# SCH_NFC-Card-Super-Shiva_2024-10-10.net
KiCad netlist of a schematic drawn in EasyEDA
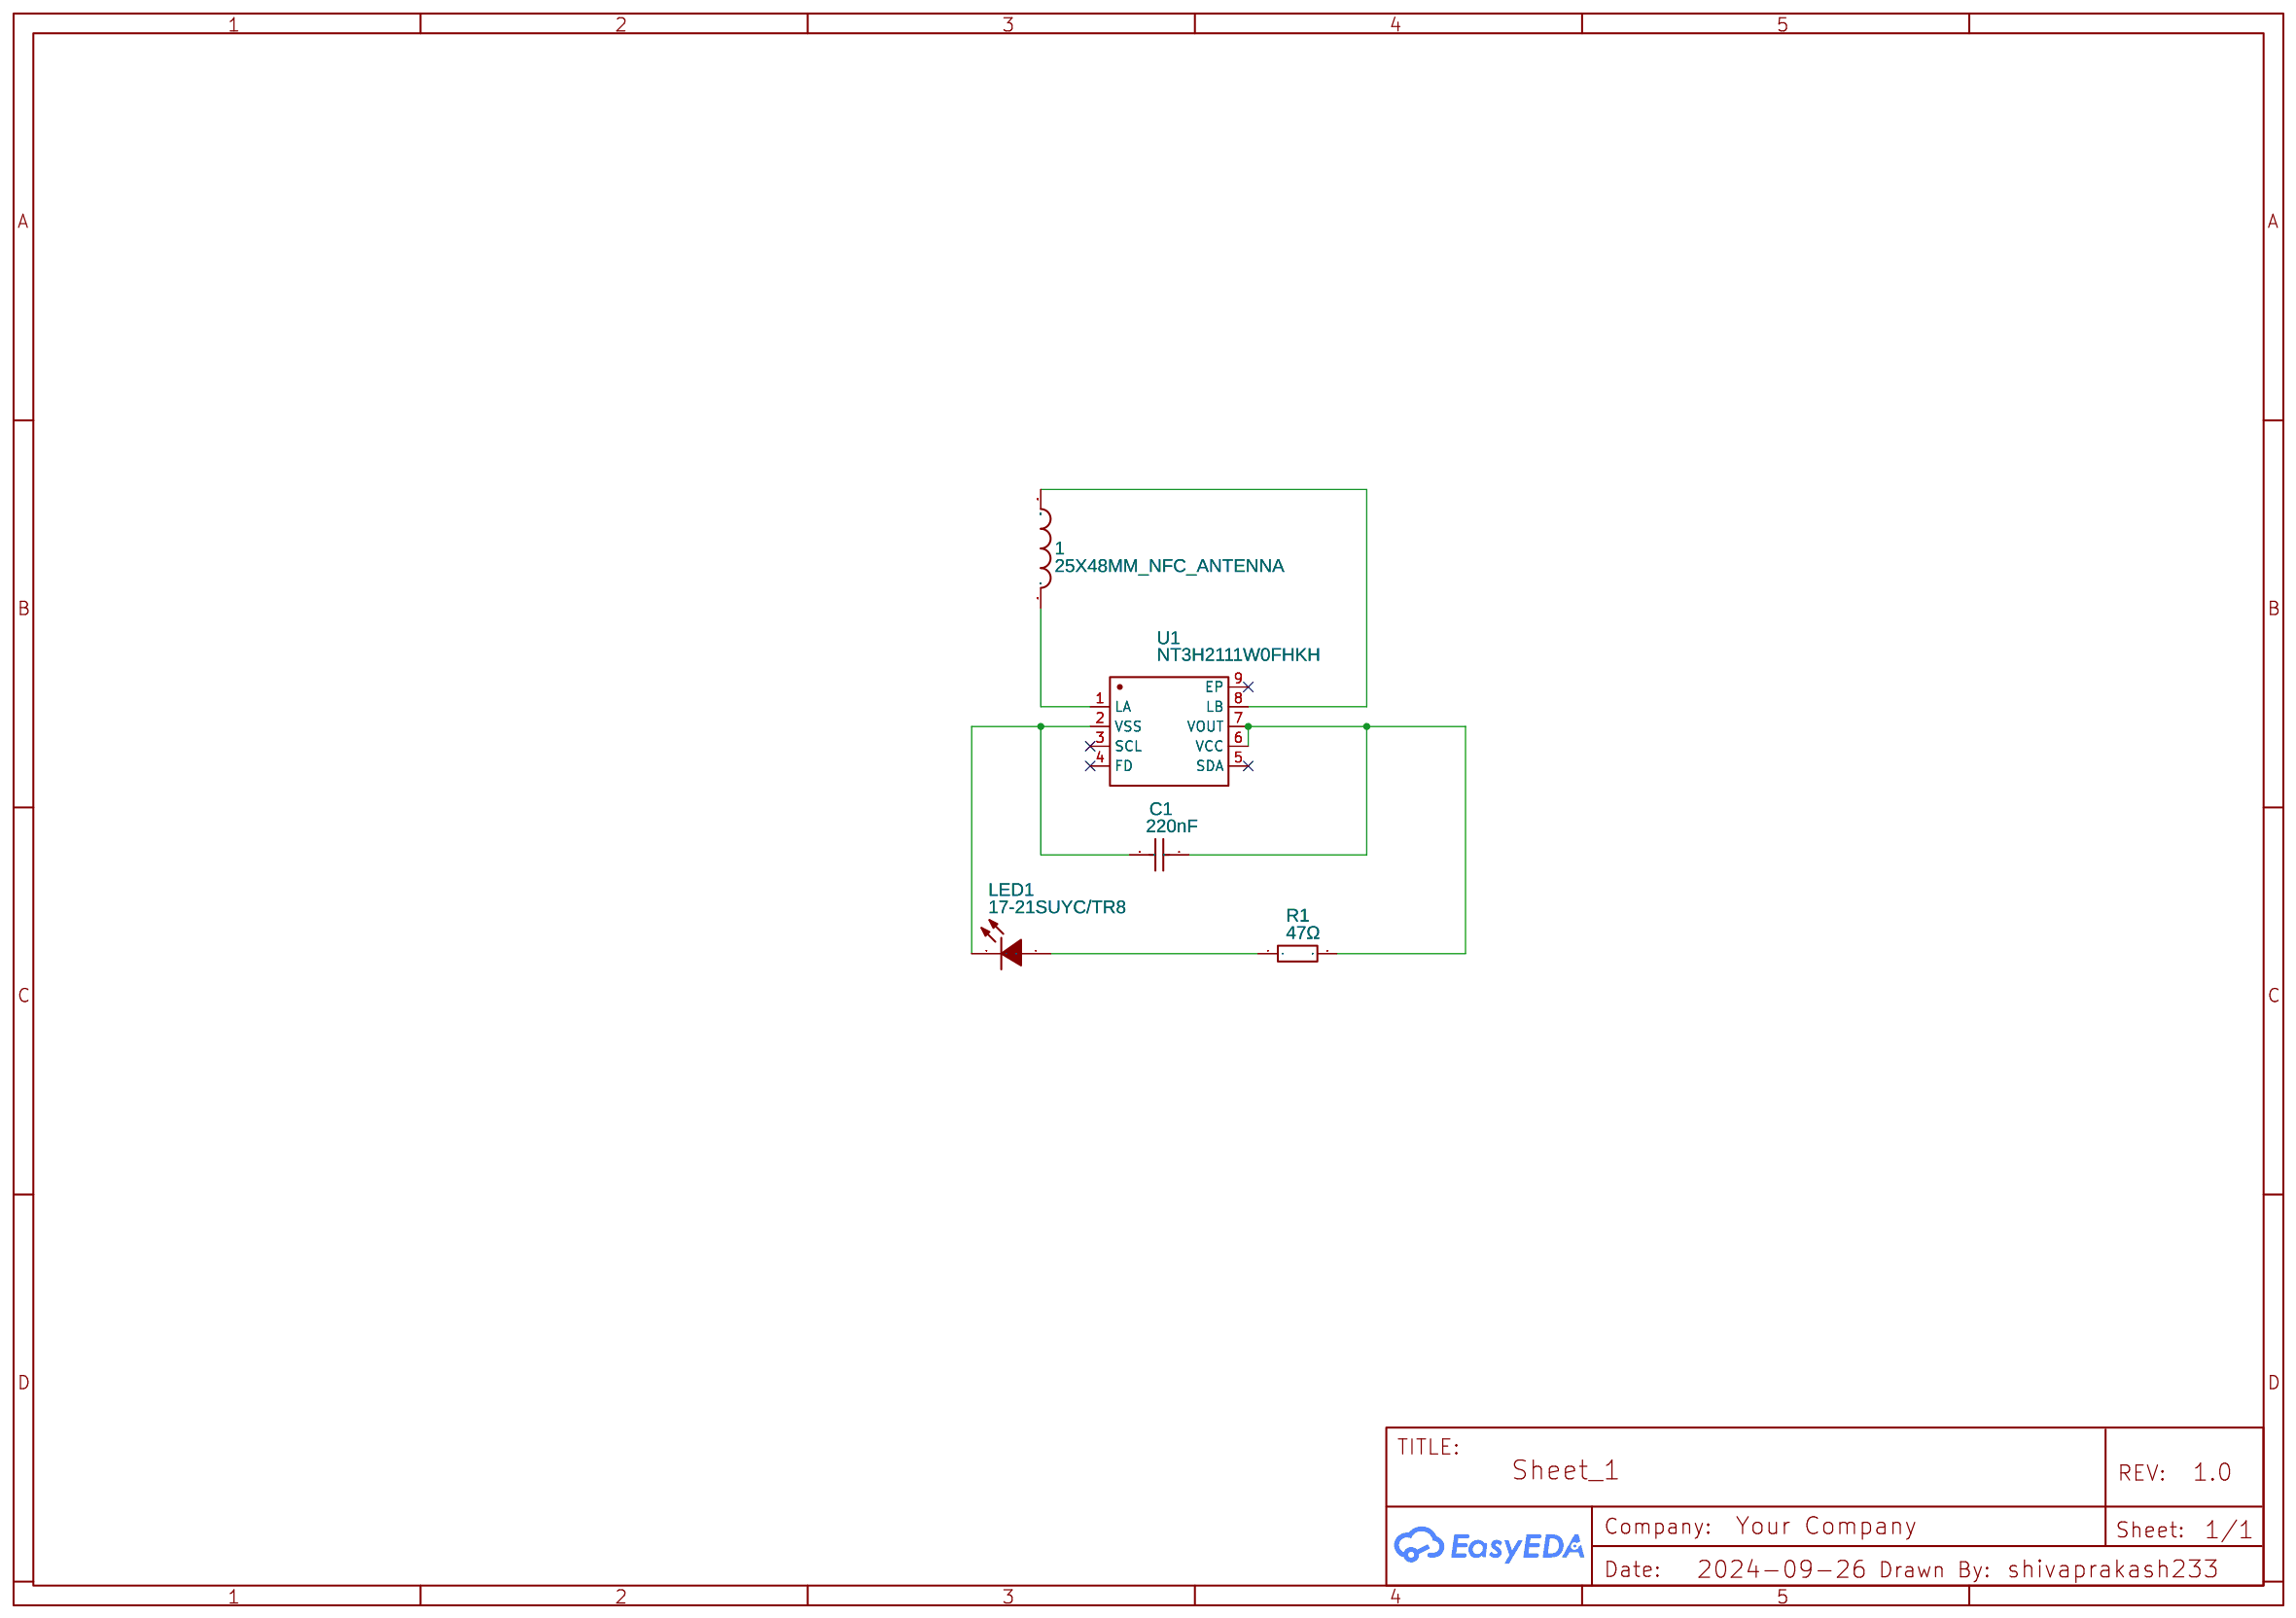
[diagram p0: schematic sheet]

(export (version "E")
  (design (tool "Eeschema 10.0.6"))
  (components
    (comp (ref "1") (value "25X48MM_NFC_ANTENNA") (libsource (lib "") (part "25X48MM_NFC_ANTENNA")))
    (comp (ref "C1")
      (value "220nF")
      (fields
        (field (name "Manufacturer Part") "CL10B224KA8NNNC")
        (field (name "Manufacturer") "SAMSUNG(三星)")
      )
      (libsource (lib "") (part "CL10B224KA8NNNC"))
    )
    (comp (ref "LED1")
      (value "17-21SUYC/TR8")
      (fields (field (name "Manufacturer Part") "KT-0805黄灯") (field (name "Manufacturer") "KENTO"))
      (libsource (lib "") (part "17-21SUYC/TR8"))
    )
    (comp (ref "R1")
      (value "47Ω")
      (fields
        (field (name "Manufacturer Part") "0603WAF470JT5E")
        (field (name "Manufacturer") "UNI-ROYAL(厚声)")
      )
      (libsource (lib "") (part "0603WAF470JT5E"))
    )
    (comp (ref "U1")
      (value "NT3H2111W0FHKH")
      (fields (field (name "Manufacturer") "NXP(恩智浦)"))
      (libsource (lib "") (part "NT3H2111W0FHKH"))
    )
  )
  (nets
    (net (code "1") (name "Net-(LED1-+)") (class "Default")
      (node (ref "LED1") (pin "1") (pinfunction "+_1") (pintype "unspecified"))
      (node (ref "R1") (pin "1") (pinfunction "1_1") (pintype "input"))
    )
    (net (code "2") (name "Net-(LED1--)") (class "Default")
      (node (ref "C1") (pin "1") (pinfunction "1_1") (pintype "input"))
      (node (ref "LED1") (pin "2") (pinfunction "-_2") (pintype "unspecified"))
      (node (ref "U1") (pin "2") (pinfunction "VSS_2") (pintype "unspecified"))
    )
    (net (code "3") (name "Net-(U1-LA)") (class "Default")
      (node (ref "1") (pin "P$2") (pinfunction "P$2_P$2") (pintype "bidirectional"))
      (node (ref "U1") (pin "1") (pinfunction "LA_1") (pintype "unspecified"))
    )
    (net (code "4") (name "Net-(U1-LB)") (class "Default")
      (node (ref "1") (pin "P$1") (pinfunction "P$1_P$1") (pintype "bidirectional"))
      (node (ref "U1") (pin "8") (pinfunction "LB_8") (pintype "unspecified"))
    )
    (net (code "5") (name "Net-(U1-VCC)") (class "Default")
      (node (ref "C1") (pin "2") (pinfunction "2_2") (pintype "input"))
      (node (ref "R1") (pin "2") (pinfunction "2_2") (pintype "input"))
      (node (ref "U1") (pin "6") (pinfunction "VCC_6") (pintype "unspecified"))
      (node (ref "U1") (pin "7") (pinfunction "VOUT_7") (pintype "unspecified"))
    )
    (net (code "6") (name "unconnected-(U1-EP-Pad9)") (class "Default")
      (node (ref "U1") (pin "9") (pinfunction "EP_9") (pintype "unspecified+no_connect"))
    )
    (net (code "7") (name "unconnected-(U1-FD-Pad4)") (class "Default")
      (node (ref "U1") (pin "4") (pinfunction "FD_4") (pintype "unspecified+no_connect"))
    )
    (net (code "8") (name "unconnected-(U1-SCL-Pad3)") (class "Default")
      (node (ref "U1") (pin "3") (pinfunction "SCL_3") (pintype "unspecified+no_connect"))
    )
    (net (code "9") (name "unconnected-(U1-SDA-Pad5)") (class "Default")
      (node (ref "U1") (pin "5") (pinfunction "SDA_5") (pintype "unspecified+no_connect"))
    )
  )
)
